# design_sch.net
KiCad netlist of a schematic drawn in EasyEDA
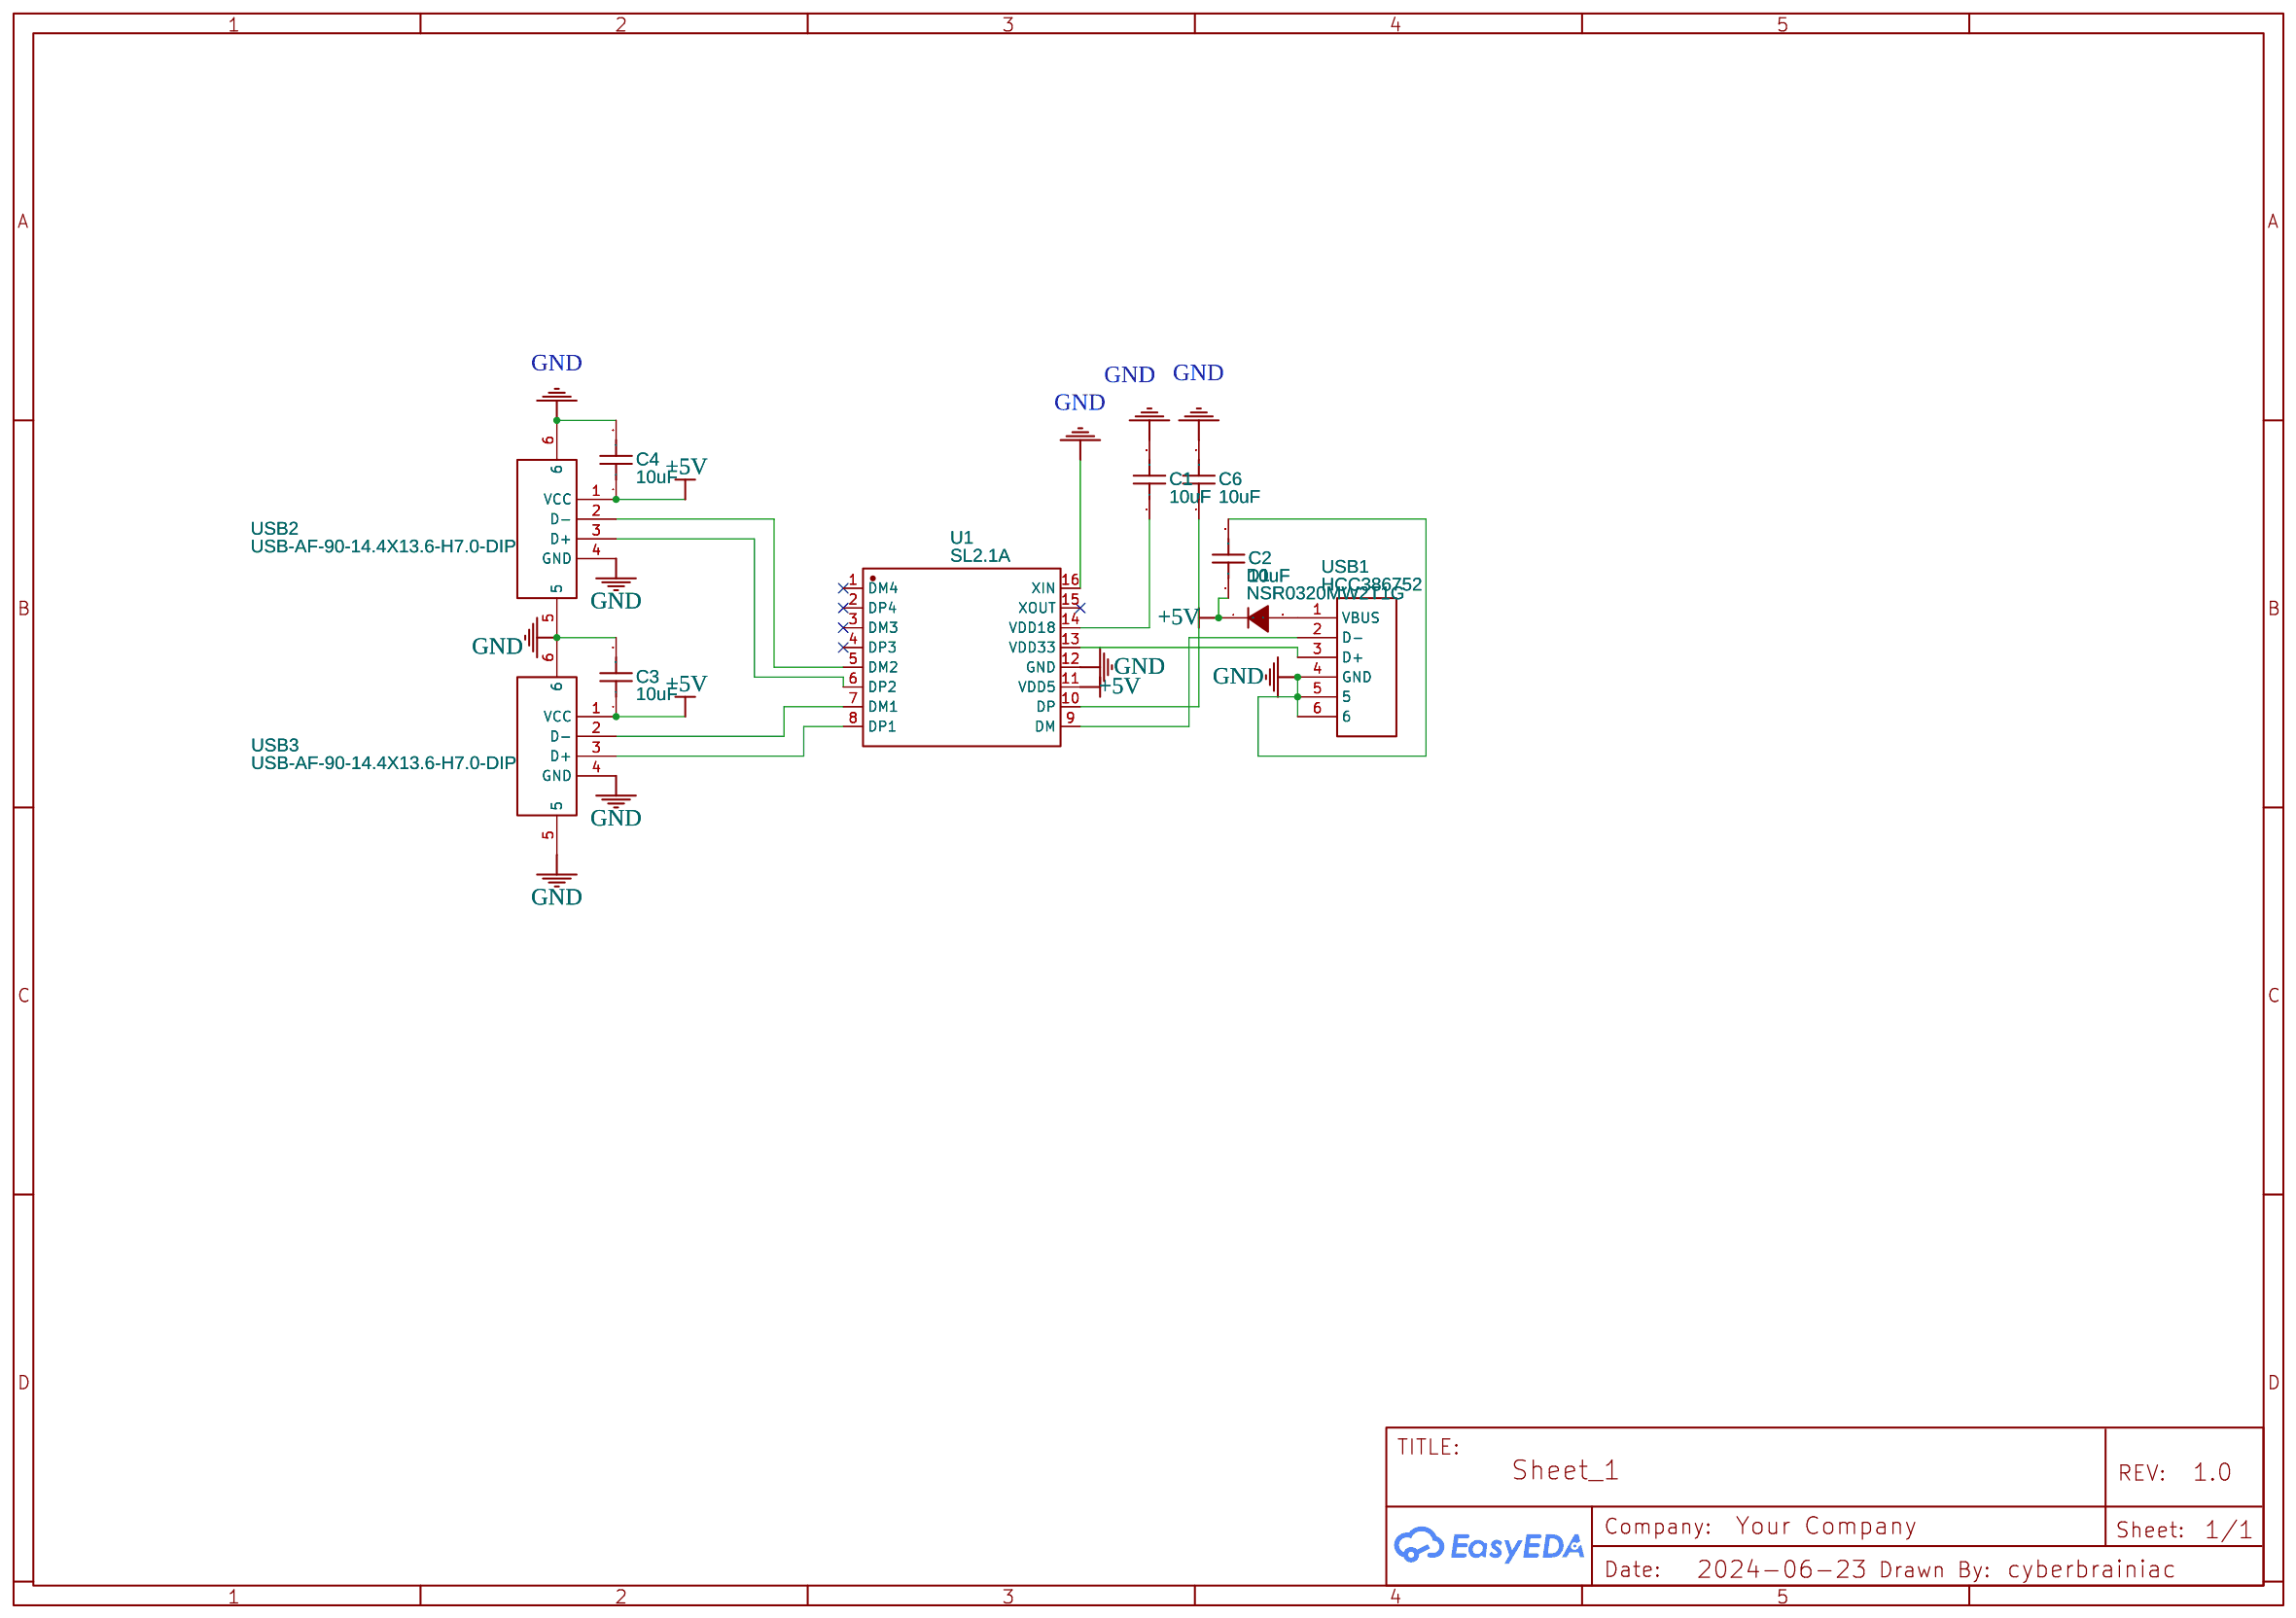
[diagram p0: schematic sheet]

(export (version "E")
  (design (tool "Eeschema 10.0.6"))
  (components
    (comp (ref "C1")
      (value "10uF")
      (fields
        (field (name "Manufacturer Part") "CL10A106KP8NNNC")
        (field (name "Manufacturer") "SAMSUNG(三星)")
      )
      (libsource (lib "") (part "CL10A106KP8NNNC"))
    )
    (comp (ref "C2")
      (value "10uF")
      (fields
        (field (name "Manufacturer Part") "CL10A106KP8NNNC")
        (field (name "Manufacturer") "SAMSUNG(三星)")
      )
      (libsource (lib "") (part "CL10A106KP8NNNC"))
    )
    (comp (ref "C3")
      (value "10uF")
      (fields
        (field (name "Manufacturer Part") "CL10A106KP8NNNC")
        (field (name "Manufacturer") "SAMSUNG(三星)")
      )
      (libsource (lib "") (part "CL10A106KP8NNNC"))
    )
    (comp (ref "C4")
      (value "10uF")
      (fields
        (field (name "Manufacturer Part") "CL10A106KP8NNNC")
        (field (name "Manufacturer") "SAMSUNG(三星)")
      )
      (libsource (lib "") (part "CL10A106KP8NNNC"))
    )
    (comp (ref "C6")
      (value "10uF")
      (fields
        (field (name "Manufacturer Part") "CL10A106KP8NNNC")
        (field (name "Manufacturer") "SAMSUNG(三星)")
      )
      (libsource (lib "") (part "CL10A106KP8NNNC"))
    )
    (comp (ref "D1")
      (value "NSR0320MW2T1G")
      (fields (field (name "Manufacturer") "onsemi(安森美)"))
      (libsource (lib "") (part "NSR0320MW2T1G"))
    )
    (comp (ref "U1")
      (value "SL2.1A")
      (fields (field (name "Manufacturer") "CoreChips(和芯润德)"))
      (libsource (lib "") (part "SL2.1A"))
    )
    (comp (ref "USB1")
      (value "HCC386752")
      (fields (field (name "Manufacturer Part") "U-USBAR04P-M003") (field (name "Manufacturer") "Ckmtw(灿科盟)"))
      (libsource (lib "") (part "HCC386752"))
    )
    (comp (ref "USB2")
      (value "USB-AF-90-14.4X13.6-H7.0-DIP")
      (fields (field (name "Manufacturer Part") "903-131A1011D10100") (field (name "Manufacturer") "精拓金"))
      (libsource (lib "") (part "USB-AF-90-14.4X13.6-H7.0-DIP"))
    )
    (comp (ref "USB3")
      (value "USB-AF-90-14.4X13.6-H7.0-DIP")
      (fields (field (name "Manufacturer Part") "903-131A1011D10100") (field (name "Manufacturer") "精拓金"))
      (libsource (lib "") (part "USB-AF-90-14.4X13.6-H7.0-DIP"))
    )
  )
  (nets
    (net (code "1") (name "+5V") (class "Default")
      (node (ref "C2") (pin "1") (pinfunction "1_1") (pintype "unspecified"))
      (node (ref "C3") (pin "1") (pinfunction "1_1") (pintype "unspecified"))
      (node (ref "C4") (pin "1") (pinfunction "1_1") (pintype "unspecified"))
      (node (ref "D1") (pin "1") (pinfunction "C_1") (pintype "unspecified"))
      (node (ref "U1") (pin "11") (pinfunction "VDD5_11") (pintype "unspecified"))
      (node (ref "USB2") (pin "1") (pinfunction "VCC_1") (pintype "unspecified"))
      (node (ref "USB3") (pin "1") (pinfunction "VCC_1") (pintype "unspecified"))
    )
    (net (code "2") (name "GND") (class "Default")
      (node (ref "C1") (pin "2") (pinfunction "2_2") (pintype "unspecified"))
      (node (ref "C2") (pin "2") (pinfunction "2_2") (pintype "unspecified"))
      (node (ref "C3") (pin "2") (pinfunction "2_2") (pintype "unspecified"))
      (node (ref "C4") (pin "2") (pinfunction "2_2") (pintype "unspecified"))
      (node (ref "C6") (pin "2") (pinfunction "2_2") (pintype "unspecified"))
      (node (ref "U1") (pin "12") (pinfunction "GND_12") (pintype "unspecified"))
      (node (ref "U1") (pin "16") (pinfunction "XIN_16") (pintype "unspecified"))
      (node (ref "USB1") (pin "4") (pinfunction "GND_4") (pintype "unspecified"))
      (node (ref "USB1") (pin "5") (pinfunction "5_5") (pintype "unspecified"))
      (node (ref "USB1") (pin "6") (pinfunction "6_6") (pintype "unspecified"))
      (node (ref "USB2") (pin "4") (pinfunction "GND_4") (pintype "unspecified"))
      (node (ref "USB2") (pin "5") (pinfunction "5_5") (pintype "unspecified"))
      (node (ref "USB2") (pin "6") (pinfunction "6_6") (pintype "unspecified"))
      (node (ref "USB3") (pin "4") (pinfunction "GND_4") (pintype "unspecified"))
      (node (ref "USB3") (pin "5") (pinfunction "5_5") (pintype "unspecified"))
      (node (ref "USB3") (pin "6") (pinfunction "6_6") (pintype "unspecified"))
    )
    (net (code "3") (name "Net-(D1-A)") (class "Default")
      (node (ref "D1") (pin "2") (pinfunction "A_2") (pintype "unspecified"))
      (node (ref "USB1") (pin "1") (pinfunction "VBUS_1") (pintype "unspecified"))
    )
    (net (code "4") (name "Net-(U1-DM)") (class "Default")
      (node (ref "U1") (pin "9") (pinfunction "DM_9") (pintype "unspecified"))
      (node (ref "USB1") (pin "2") (pinfunction "D-_2") (pintype "unspecified"))
    )
    (net (code "5") (name "Net-(U1-DM1)") (class "Default")
      (node (ref "U1") (pin "7") (pinfunction "DM1_7") (pintype "unspecified"))
      (node (ref "USB3") (pin "2") (pinfunction "D-_2") (pintype "unspecified"))
    )
    (net (code "6") (name "Net-(U1-DM2)") (class "Default")
      (node (ref "U1") (pin "5") (pinfunction "DM2_5") (pintype "unspecified"))
      (node (ref "USB2") (pin "2") (pinfunction "D-_2") (pintype "unspecified"))
    )
    (net (code "7") (name "Net-(U1-DP)") (class "Default")
      (node (ref "C6") (pin "1") (pinfunction "1_1") (pintype "unspecified"))
      (node (ref "U1") (pin "10") (pinfunction "DP_10") (pintype "unspecified"))
      (node (ref "U1") (pin "13") (pinfunction "VDD33_13") (pintype "unspecified"))
      (node (ref "USB1") (pin "3") (pinfunction "D+_3") (pintype "unspecified"))
    )
    (net (code "8") (name "Net-(U1-DP1)") (class "Default")
      (node (ref "U1") (pin "8") (pinfunction "DP1_8") (pintype "unspecified"))
      (node (ref "USB3") (pin "3") (pinfunction "D+_3") (pintype "unspecified"))
    )
    (net (code "9") (name "Net-(U1-DP2)") (class "Default")
      (node (ref "U1") (pin "6") (pinfunction "DP2_6") (pintype "unspecified"))
      (node (ref "USB2") (pin "3") (pinfunction "D+_3") (pintype "unspecified"))
    )
    (net (code "10") (name "Net-(U1-VDD18)") (class "Default")
      (node (ref "C1") (pin "1") (pinfunction "1_1") (pintype "unspecified"))
      (node (ref "U1") (pin "14") (pinfunction "VDD18_14") (pintype "unspecified"))
    )
    (net (code "11") (name "unconnected-(U1-DM3-Pad3)") (class "Default")
      (node (ref "U1") (pin "3") (pinfunction "DM3_3") (pintype "unspecified+no_connect"))
    )
    (net (code "12") (name "unconnected-(U1-DM4-Pad1)") (class "Default")
      (node (ref "U1") (pin "1") (pinfunction "DM4_1") (pintype "unspecified+no_connect"))
    )
    (net (code "13") (name "unconnected-(U1-DP3-Pad4)") (class "Default")
      (node (ref "U1") (pin "4") (pinfunction "DP3_4") (pintype "unspecified+no_connect"))
    )
    (net (code "14") (name "unconnected-(U1-DP4-Pad2)") (class "Default")
      (node (ref "U1") (pin "2") (pinfunction "DP4_2") (pintype "unspecified+no_connect"))
    )
    (net (code "15") (name "unconnected-(U1-XOUT-Pad15)") (class "Default")
      (node (ref "U1") (pin "15") (pinfunction "XOUT_15") (pintype "unspecified+no_connect"))
    )
  )
)
